# Charger.net
KiCad netlist of a schematic drawn in Altium Designer
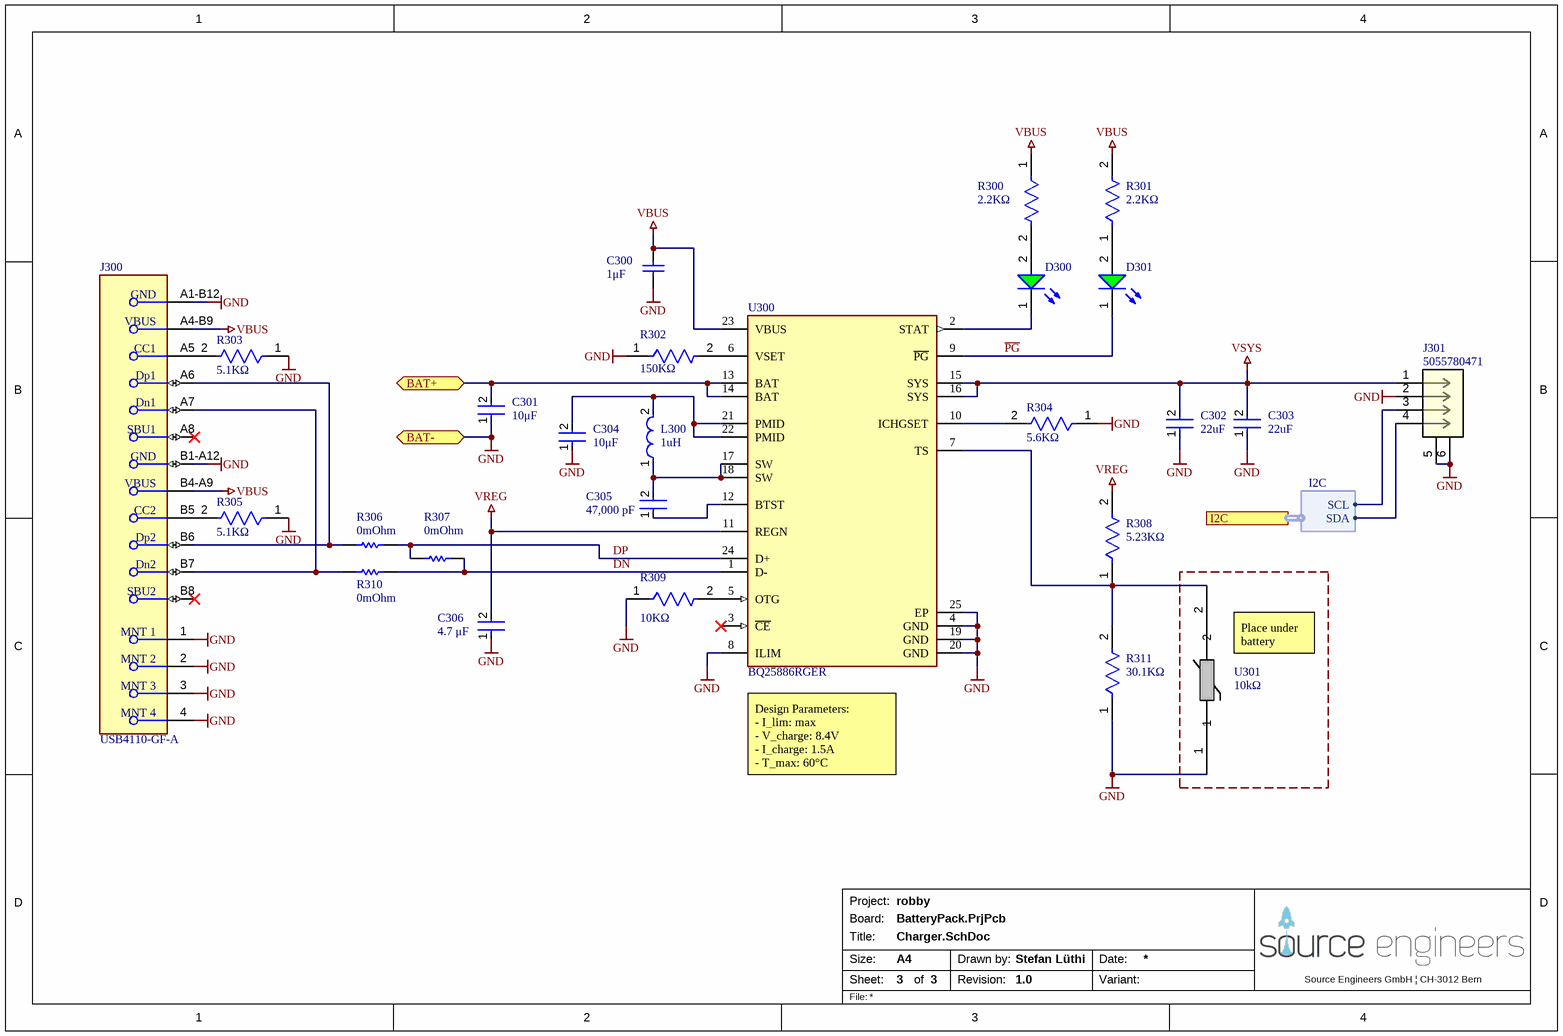
[diagram p0: Charger.SchDoc]

(export (version "E")
  (design (tool "Eeschema 10.0.6"))
  (components
    (comp (ref "C300")
      (value "GRM219R71E105KA88D")
      (footprint "CAPC2013X95X45NL10T25")
      (fields (field (name "MANUFACTURER") "Murata") (field (name "PARAMETER 1") "1μF"))
      (libsource (lib "Altium Content Vault") (part "CAP"))
    )
    (comp (ref "C301")
      (value "10μF")
      (footprint "FP-GRM31C-0_2-e0_3_0_8-IPC_B")
      (description "Chip Multilayer Ceramic Capacitors for General Purpose, 1206, 10uF, X7R, 15%, 20%, 25V")
      (fields (field (name "Comment") "GRM31CR71E106MA12K"))
      (libsource (lib "Altium Content Vault") (part "02cd4be3c70576c341d710602a673aa"))
    )
    (comp (ref "C302")
      (value "GRM32ER71E226ME15K")
      (footprint "FP-GRM32E-0_3-0_2-MFG")
      (description "Chip Multilayer Ceramic Capacitors for General Purpose, 1210, 22uF, X7R, 15%, 20%, 25V")
      (fields
        (field (name "TOLERANCE") "20%")
        (field (name "CAPACITANCE") "22uF")
        (field (name "VOLTAGE") "25V")
      )
      (libsource (lib "Altium Content Vault") (part "02cd4be3c70576c341d710602a673aa"))
    )
    (comp (ref "C303")
      (value "GRM32ER71E226ME15K")
      (footprint "FP-GRM32E-0_3-0_2-MFG")
      (description "Chip Multilayer Ceramic Capacitors for General Purpose, 1210, 22uF, X7R, 15%, 20%, 25V")
      (fields
        (field (name "TOLERANCE") "20%")
        (field (name "CAPACITANCE") "22uF")
        (field (name "VOLTAGE") "25V")
      )
      (libsource (lib "Altium Content Vault") (part "02cd4be3c70576c341d710602a673aa"))
    )
    (comp (ref "C304")
      (value "10μF")
      (footprint "FP-GRM31C-0_2-e0_3_0_8-IPC_B")
      (description "Chip Multilayer Ceramic Capacitors for General Purpose, 1206, 10uF, X7R, 15%, 20%, 25V")
      (fields (field (name "Comment") "GRM31CR71E106MA12K"))
      (libsource (lib "Altium Content Vault") (part "02cd4be3c70576c341d710602a673aa"))
    )
    (comp (ref "C305")
      (value "47,000 pF")
      (footprint "FP-C0603C-CF-MFG")
      (description "CAP CER 0.047UF 50V X7R 0603")
      (fields
        (field (name "MANUFACTURER PART NUMBER") "C0603C473M5RACTU")
        (field (name "MANUFACTURER") "KEMET")
      )
      (libsource (lib "Altium Content Vault") (part "b4654b650e69147ec39a6b967a45e02"))
    )
    (comp (ref "C306")
      (value "GRM188Z71A475ME15D")
      (footprint "FP-GRM188-0_15-IPC_B")
      (description "Chip Multilayer Ceramic Capacitors for General Purpose, 0603, 4.7uF, X7R, 15%, 20%, 10V")
      (fields (field (name "PARAMETER 1") "4.7 μF"))
      (libsource (lib "Altium Content Vault") (part "02cd4be3c70576c341d710602a673aa"))
    )
    (comp (ref "D300")
      (value "155060VS75300")
      (footprint "WL-SMSW_0603_L1.6W0.98H0.8")
      (description "155060VS75300 Led, Green, 60Mcd, 570Nm Rohs Compliant: Yes")
      (libsource (lib "Altium Content Vault") (part "LED_Green_2A-1K"))
    )
    (comp (ref "D301")
      (value "155060VS75300")
      (footprint "WL-SMSW_0603_L1.6W0.98H0.8")
      (description "155060VS75300 Led, Green, 60Mcd, 570Nm Rohs Compliant: Yes")
      (libsource (lib "Altium Content Vault") (part "LED_Green_2A-1K"))
    )
    (comp (ref "J300")
      (value "USB4110-GF-A")
      (footprint "FP-USB4110-GF-A-MFG")
      (description "CONN USB 2.0 TYPE-C R/A SMT")
      (fields
        (field (name "OCTOPART") "https://octopart.com/usb4110-gf-a-gct-103941985")
        (field (name "MANUFACTURER") "GCT")
      )
      (libsource (lib "Altium Content Vault") (part "e23f2b38bb3c3f98e683ebab9ede730"))
    )
    (comp (ref "J301")
      (value "5055780471")
      (footprint "CONN_505578_04_MOL")
      (fields (field (name "COPYRIGHT") "Copyright (C) 2025 Ultra Librarian. All rights reserved."))
      (libsource (lib "robby") (part "5055780471"))
    )
    (comp (ref "L300")
      (value "IHLP2525CZER1R0M01")
      (footprint "FP-IHLP-2525CZ-FP_2_413x3-MFG")
      (description "Commercial Inductors, High Saturation Series 1uH 11A 10mΩ 20%")
      (fields (field (name "TOLERANCE") "20%") (field (name "INDUCTANCE") "1uH"))
      (libsource (lib "Altium Content Vault") (part "725321dda6339637d4d059423bc1c3c"))
    )
    (comp (ref "R300")
      (value "2.2KΩ")
      (footprint "FP-RT0603-MFG")
      (description "RES SMD 2.2K OHM 1% 1/10W 0603")
      (fields
        (field (name "MANUFACTURER") "Yageo")
        (field (name "OCTOPART") "https://octopart.com/rt0603fre072k2l-yageo-40019811")
      )
      (libsource (lib "Altium Content Vault") (part "1029c3af85768c4190bb7ad29bc67b5"))
    )
    (comp (ref "R301")
      (value "2.2KΩ")
      (footprint "FP-RT0603-MFG")
      (description "RES SMD 2.2K OHM 1% 1/10W 0603")
      (fields
        (field (name "MANUFACTURER") "Yageo")
        (field (name "OCTOPART") "https://octopart.com/rt0603fre072k2l-yageo-40019811")
      )
      (libsource (lib "Altium Content Vault") (part "1029c3af85768c4190bb7ad29bc67b5"))
    )
    (comp (ref "R302")
      (value "150KΩ")
      (footprint "FP-RT0603-MFG")
      (description "RES SMD 150K OHM 1% 1/10W 0603")
      (fields (field (name "MANUFACTURER") "Yageo") (field (name "TOLERANCE") "0.01"))
      (libsource (lib "Altium Content Vault") (part "1029c3af85768c4190bb7ad29bc67b5"))
    )
    (comp (ref "R303")
      (value "RT0603FRE075K1L")
      (footprint "FP-RT0603-MFG")
      (description "RES SMD 5.1K OHM 1% 1/10W 0603")
      (fields
        (field (name "RESISTANCE") "5.1KΩ")
        (field (name "MANUFACTURER") "Yageo")
        (field (name "OCTOPART") "https://octopart.com/rt0603fre075k1l-yageo-1421390")
      )
      (libsource (lib "Altium Content Vault") (part "1029c3af85768c4190bb7ad29bc67b5"))
    )
    (comp (ref "R304")
      (value "5.6KΩ")
      (footprint "FP-RT0603-MFG")
      (description "RES SMD 5.6K OHM 1% 1/10W 0603")
      (fields (field (name "MANUFACTURER PART NUMBER") "RT0603FRE075K6L") (field (name "TOLERANCE") "0.01"))
      (libsource (lib "Altium Content Vault") (part "1029c3af85768c4190bb7ad29bc67b5"))
    )
    (comp (ref "R305")
      (value "RT0603FRE075K1L")
      (footprint "FP-RT0603-MFG")
      (description "RES SMD 5.1K OHM 1% 1/10W 0603")
      (fields
        (field (name "RESISTANCE") "5.1KΩ")
        (field (name "MANUFACTURER") "Yageo")
        (field (name "OCTOPART") "https://octopart.com/rt0603fre075k1l-yageo-1421390")
      )
      (libsource (lib "Altium Content Vault") (part "1029c3af85768c4190bb7ad29bc67b5"))
    )
    (comp (ref "R306")
      (value "RC0603JR-070RL")
      (footprint "RESC1608X55X25ML10T15")
      (description "Chip Resistor, 0 Ohm, +/- 5%, 0.1 W, -55 to 155 degC, 0603 (1608 Metric), RoHS, Tape and Reel")
      (fields
        (field (name "TOLERANCE") "5%")
        (field (name "RESISTANCE") "0mOhm")
        (field (name "MANUFACTURER") "Yageo")
      )
      (libsource (lib "Altium Content Vault") (part "RES-2"))
    )
    (comp (ref "R307")
      (value "RC0603JR-070RL")
      (footprint "RESC1608X55X25ML10T15")
      (description "Chip Resistor, 0 Ohm, +/- 5%, 0.1 W, -55 to 155 degC, 0603 (1608 Metric), RoHS, Tape and Reel")
      (fields
        (field (name "TOLERANCE") "5%")
        (field (name "RESISTANCE") "0mOhm")
        (field (name "MANUFACTURER") "Yageo")
      )
      (libsource (lib "Altium Content Vault") (part "RES-2"))
    )
    (comp (ref "R308")
      (value "5.23KΩ")
      (footprint "FP-RT0603-MFG")
      (description "RES SMD 5.23K OHM 1% 1/10W 0603")
      (fields
        (field (name "OCTOPART") "https://octopart.com/rt0603fre075k23l-yageo-1422860")
        (field (name "MANUFACTURER PART NUMBER") "RT0603FRE075K23L")
      )
      (libsource (lib "Altium Content Vault") (part "1029c3af85768c4190bb7ad29bc67b5"))
    )
    (comp (ref "R309")
      (value "10KΩ")
      (footprint "FP-RT0603-MFG")
      (description "RES SMD 10K OHM 1% 1/10W 0603")
      (fields
        (field (name "MANUFACTURER") "Yageo")
        (field (name "OCTOPART") "https://octopart.com/rt0603fre0710kl-yageo-40009243")
      )
      (libsource (lib "Altium Content Vault") (part "1029c3af85768c4190bb7ad29bc67b5"))
    )
    (comp (ref "R310")
      (value "RC0603JR-070RL")
      (footprint "RESC1608X55X25ML10T15")
      (description "Chip Resistor, 0 Ohm, +/- 5%, 0.1 W, -55 to 155 degC, 0603 (1608 Metric), RoHS, Tape and Reel")
      (fields
        (field (name "TOLERANCE") "5%")
        (field (name "RESISTANCE") "0mOhm")
        (field (name "MANUFACTURER") "Yageo")
      )
      (libsource (lib "Altium Content Vault") (part "RES-2"))
    )
    (comp (ref "R311")
      (value "30.1KΩ")
      (footprint "FP-RT0603-MFG")
      (description "RES SMD 30.1K OHM 1% 1/10W 0603")
      (fields
        (field (name "OCTOPART") "https://octopart.com/rt0603fre0730k1l-yageo-1278177")
        (field (name "MANUFACTURER") "Yageo")
      )
      (libsource (lib "Altium Content Vault") (part "1029c3af85768c4190bb7ad29bc67b5"))
    )
    (comp (ref "U300")
      (value "BQ25886RGER")
      (footprint "FP-RGE0024H-IPC_C")
      (description "PWR MGMT BATTERY MGMT")
      (libsource (lib "Altium Content Vault") (part "89915a63032611fcbc02831425e9645"))
    )
    (comp (ref "U301")
      (value "NTCS0603E3103FLT")
      (footprint "NTCS0603_VIS")
      (description "THERMISTOR NTC 10KOHM 3435K 0603")
      (fields (field (name "TOLERANCE") "1%") (field (name "RESISTANCE") "10kΩ"))
      (libsource (lib "Altium Content Vault") (part "NTCS0603E3103FLT"))
    )
  )
  (nets
    (net (code "2") (name "/BAT+") (class "Default")
      (node (ref "C301") (pin "2") (pinfunction "2_2") (pintype "passive"))
      (node (ref "U300") (pin "13") (pinfunction "BAT_13") (pintype "power_in"))
      (node (ref "U300") (pin "14") (pinfunction "BAT_14") (pintype "power_in"))
    )
    (net (code "3") (name "/DN") (class "Default")
      (node (ref "R307") (pin "1") (pinfunction "1_1") (pintype "passive"))
      (node (ref "R310") (pin "1") (pinfunction "1_1") (pintype "passive"))
      (node (ref "U300") (pin "1") (pinfunction "D-_1") (pintype "passive"))
    )
    (net (code "4") (name "/DP") (class "Default")
      (node (ref "R306") (pin "1") (pinfunction "1_1") (pintype "passive"))
      (node (ref "R307") (pin "2") (pinfunction "2_2") (pintype "passive"))
      (node (ref "U300") (pin "24") (pinfunction "D+_24") (pintype "passive"))
    )
    (net (code "5") (name "/SCL") (class "Default")
      (node (ref "J301") (pin "3") (pinfunction "3_3") (pintype "passive"))
    )
    (net (code "6") (name "/SDA") (class "Default")
      (node (ref "J301") (pin "4") (pinfunction "4_4") (pintype "passive"))
    )
    (net (code "8") (name "/~{PG}") (class "Default")
      (node (ref "D301") (pin "1") (pinfunction "K_1") (pintype "passive"))
      (node (ref "U300") (pin "9") (pinfunction "~{PG}_9") (pintype "open_collector"))
    )
    (net (code "9") (name "GND") (class "Default")
      (node (ref "C300") (pin "1") (pinfunction "1_1") (pintype "passive"))
      (node (ref "C301") (pin "1") (pinfunction "1_1") (pintype "passive"))
      (node (ref "C302") (pin "1") (pinfunction "1_1") (pintype "passive"))
      (node (ref "C303") (pin "1") (pinfunction "1_1") (pintype "passive"))
      (node (ref "C304") (pin "1") (pinfunction "1_1") (pintype "passive"))
      (node (ref "C306") (pin "1") (pinfunction "1_1") (pintype "passive"))
      (node (ref "J300") (pin "1") (pinfunction "MNT_1_1") (pintype "passive"))
      (node (ref "J300") (pin "2") (pinfunction "MNT_2_2") (pintype "passive"))
      (node (ref "J300") (pin "3") (pinfunction "MNT_3_3") (pintype "passive"))
      (node (ref "J300") (pin "4") (pinfunction "MNT_4_4") (pintype "passive"))
      (node (ref "J300") (pin "A1-B12") (pinfunction "GND_A1-B12") (pintype "passive"))
      (node (ref "J300") (pin "B1-A12") (pinfunction "GND_B1-A12") (pintype "bidirectional"))
      (node (ref "J301") (pin "2") (pinfunction "2_2") (pintype "passive"))
      (node (ref "J301") (pin "5") (pinfunction "5_5") (pintype "passive"))
      (node (ref "J301") (pin "6") (pinfunction "6_6") (pintype "passive"))
      (node (ref "R302") (pin "1") (pinfunction "1_1") (pintype "passive"))
      (node (ref "R303") (pin "1") (pinfunction "1_1") (pintype "passive"))
      (node (ref "R304") (pin "1") (pinfunction "1_1") (pintype "passive"))
      (node (ref "R305") (pin "1") (pinfunction "1_1") (pintype "passive"))
      (node (ref "R309") (pin "1") (pinfunction "1_1") (pintype "passive"))
      (node (ref "R311") (pin "1") (pinfunction "1_1") (pintype "passive"))
      (node (ref "U300") (pin "19") (pinfunction "GND_19") (pintype "power_in"))
      (node (ref "U300") (pin "20") (pinfunction "GND_20") (pintype "power_in"))
      (node (ref "U300") (pin "25") (pinfunction "EP_25") (pintype "power_in"))
      (node (ref "U300") (pin "4") (pinfunction "GND_4") (pintype "power_in"))
      (node (ref "U300") (pin "8") (pinfunction "ILIM_8") (pintype "passive"))
      (node (ref "U301") (pin "1") (pinfunction "1_1") (pintype "passive"))
    )
    (net (code "10") (name "Net-(C304-Pad2)") (class "Default")
      (node (ref "C304") (pin "2") (pinfunction "2_2") (pintype "passive"))
      (node (ref "L300") (pin "2") (pinfunction "2_2") (pintype "passive"))
      (node (ref "U300") (pin "21") (pinfunction "PMID_21") (pintype "power_in"))
      (node (ref "U300") (pin "22") (pinfunction "PMID_22") (pintype "power_in"))
    )
    (net (code "11") (name "Net-(C305-Pad2)") (class "Default")
      (node (ref "C305") (pin "2") (pinfunction "2_2") (pintype "passive"))
      (node (ref "L300") (pin "1") (pinfunction "1_1") (pintype "passive"))
      (node (ref "U300") (pin "17") (pinfunction "SW_17") (pintype "power_in"))
      (node (ref "U300") (pin "18") (pinfunction "SW_18") (pintype "power_in"))
    )
    (net (code "12") (name "Net-(D300-A)") (class "Default")
      (node (ref "D300") (pin "2") (pinfunction "A_2") (pintype "passive"))
      (node (ref "R300") (pin "2") (pinfunction "2_2") (pintype "passive"))
    )
    (net (code "13") (name "Net-(D300-K)") (class "Default")
      (node (ref "D300") (pin "1") (pinfunction "K_1") (pintype "passive"))
      (node (ref "U300") (pin "2") (pinfunction "STAT_2") (pintype "output"))
    )
    (net (code "14") (name "Net-(D301-A)") (class "Default")
      (node (ref "D301") (pin "2") (pinfunction "A_2") (pintype "passive"))
      (node (ref "R301") (pin "1") (pinfunction "1_1") (pintype "passive"))
    )
    (net (code "15") (name "Net-(J300-CC1)") (class "Default")
      (node (ref "J300") (pin "A5") (pinfunction "CC1_A5") (pintype "power_in"))
      (node (ref "R303") (pin "2") (pinfunction "2_2") (pintype "passive"))
    )
    (net (code "16") (name "Net-(J300-CC2)") (class "Default")
      (node (ref "J300") (pin "B5") (pinfunction "CC2_B5") (pintype "power_in"))
      (node (ref "R305") (pin "2") (pinfunction "2_2") (pintype "passive"))
    )
    (net (code "17") (name "Net-(J300-Dn1)") (class "Default")
      (node (ref "J300") (pin "A7") (pinfunction "Dn1_A7") (pintype "bidirectional"))
      (node (ref "J300") (pin "B7") (pinfunction "Dn2_B7") (pintype "bidirectional"))
      (node (ref "R310") (pin "2") (pinfunction "2_2") (pintype "passive"))
    )
    (net (code "18") (name "Net-(J300-Dp1)") (class "Default")
      (node (ref "J300") (pin "A6") (pinfunction "Dp1_A6") (pintype "bidirectional"))
      (node (ref "J300") (pin "B6") (pinfunction "Dp2_B6") (pintype "bidirectional"))
      (node (ref "R306") (pin "2") (pinfunction "2_2") (pintype "passive"))
    )
    (net (code "19") (name "Net-(U300-BTST)") (class "Default")
      (node (ref "C305") (pin "1") (pinfunction "1_1") (pintype "passive"))
      (node (ref "U300") (pin "12") (pinfunction "BTST_12") (pintype "power_in"))
    )
    (net (code "20") (name "Net-(U300-ICHGSET)") (class "Default")
      (node (ref "R304") (pin "2") (pinfunction "2_2") (pintype "passive"))
      (node (ref "U300") (pin "10") (pinfunction "ICHGSET_10") (pintype "passive"))
    )
    (net (code "21") (name "Net-(U300-OTG)") (class "Default")
      (node (ref "R309") (pin "2") (pinfunction "2_2") (pintype "passive"))
      (node (ref "U300") (pin "5") (pinfunction "OTG_5") (pintype "input"))
    )
    (net (code "22") (name "Net-(U300-TS)") (class "Default")
      (node (ref "R308") (pin "1") (pinfunction "1_1") (pintype "passive"))
      (node (ref "R311") (pin "2") (pinfunction "2_2") (pintype "passive"))
      (node (ref "U300") (pin "7") (pinfunction "TS_7") (pintype "passive"))
      (node (ref "U301") (pin "2") (pinfunction "2_2") (pintype "passive"))
    )
    (net (code "23") (name "Net-(U300-VSET)") (class "Default")
      (node (ref "R302") (pin "2") (pinfunction "2_2") (pintype "passive"))
      (node (ref "U300") (pin "6") (pinfunction "VSET_6") (pintype "passive"))
    )
    (net (code "24") (name "VBUS") (class "Default")
      (node (ref "C300") (pin "2") (pinfunction "2_2") (pintype "passive"))
      (node (ref "J300") (pin "A4-B9") (pinfunction "VBUS_A4-B9") (pintype "power_in"))
      (node (ref "J300") (pin "B4-A9") (pinfunction "VBUS_B4-A9") (pintype "power_in"))
      (node (ref "R300") (pin "1") (pinfunction "1_1") (pintype "passive"))
      (node (ref "R301") (pin "2") (pinfunction "2_2") (pintype "passive"))
      (node (ref "U300") (pin "23") (pinfunction "VBUS_23") (pintype "power_in"))
    )
    (net (code "25") (name "VREG") (class "Default")
      (node (ref "C306") (pin "2") (pinfunction "2_2") (pintype "passive"))
      (node (ref "R308") (pin "2") (pinfunction "2_2") (pintype "passive"))
      (node (ref "U300") (pin "11") (pinfunction "REGN_11") (pintype "power_in"))
    )
    (net (code "26") (name "VSYS") (class "Default")
      (node (ref "C302") (pin "2") (pinfunction "2_2") (pintype "passive"))
      (node (ref "C303") (pin "2") (pinfunction "2_2") (pintype "passive"))
      (node (ref "J301") (pin "1") (pinfunction "1_1") (pintype "passive"))
      (node (ref "U300") (pin "15") (pinfunction "SYS_15") (pintype "power_in"))
      (node (ref "U300") (pin "16") (pinfunction "SYS_16") (pintype "power_in"))
    )
    (net (code "27") (name "unconnected-(J300-SBU1-PadA8)") (class "Default")
      (node (ref "J300") (pin "A8") (pinfunction "SBU1_A8") (pintype "bidirectional+no_connect"))
    )
    (net (code "28") (name "unconnected-(J300-SBU2-PadB8)") (class "Default")
      (node (ref "J300") (pin "B8") (pinfunction "SBU2_B8") (pintype "bidirectional+no_connect"))
    )
    (net (code "29") (name "unconnected-(U300-~{CE}-Pad3)") (class "Default")
      (node (ref "U300") (pin "3") (pinfunction "~{CE}_3") (pintype "input+no_connect"))
    )
  )
)
